# ir-tara-h.net
KiCad netlist of a schematic drawn in Altium Designer
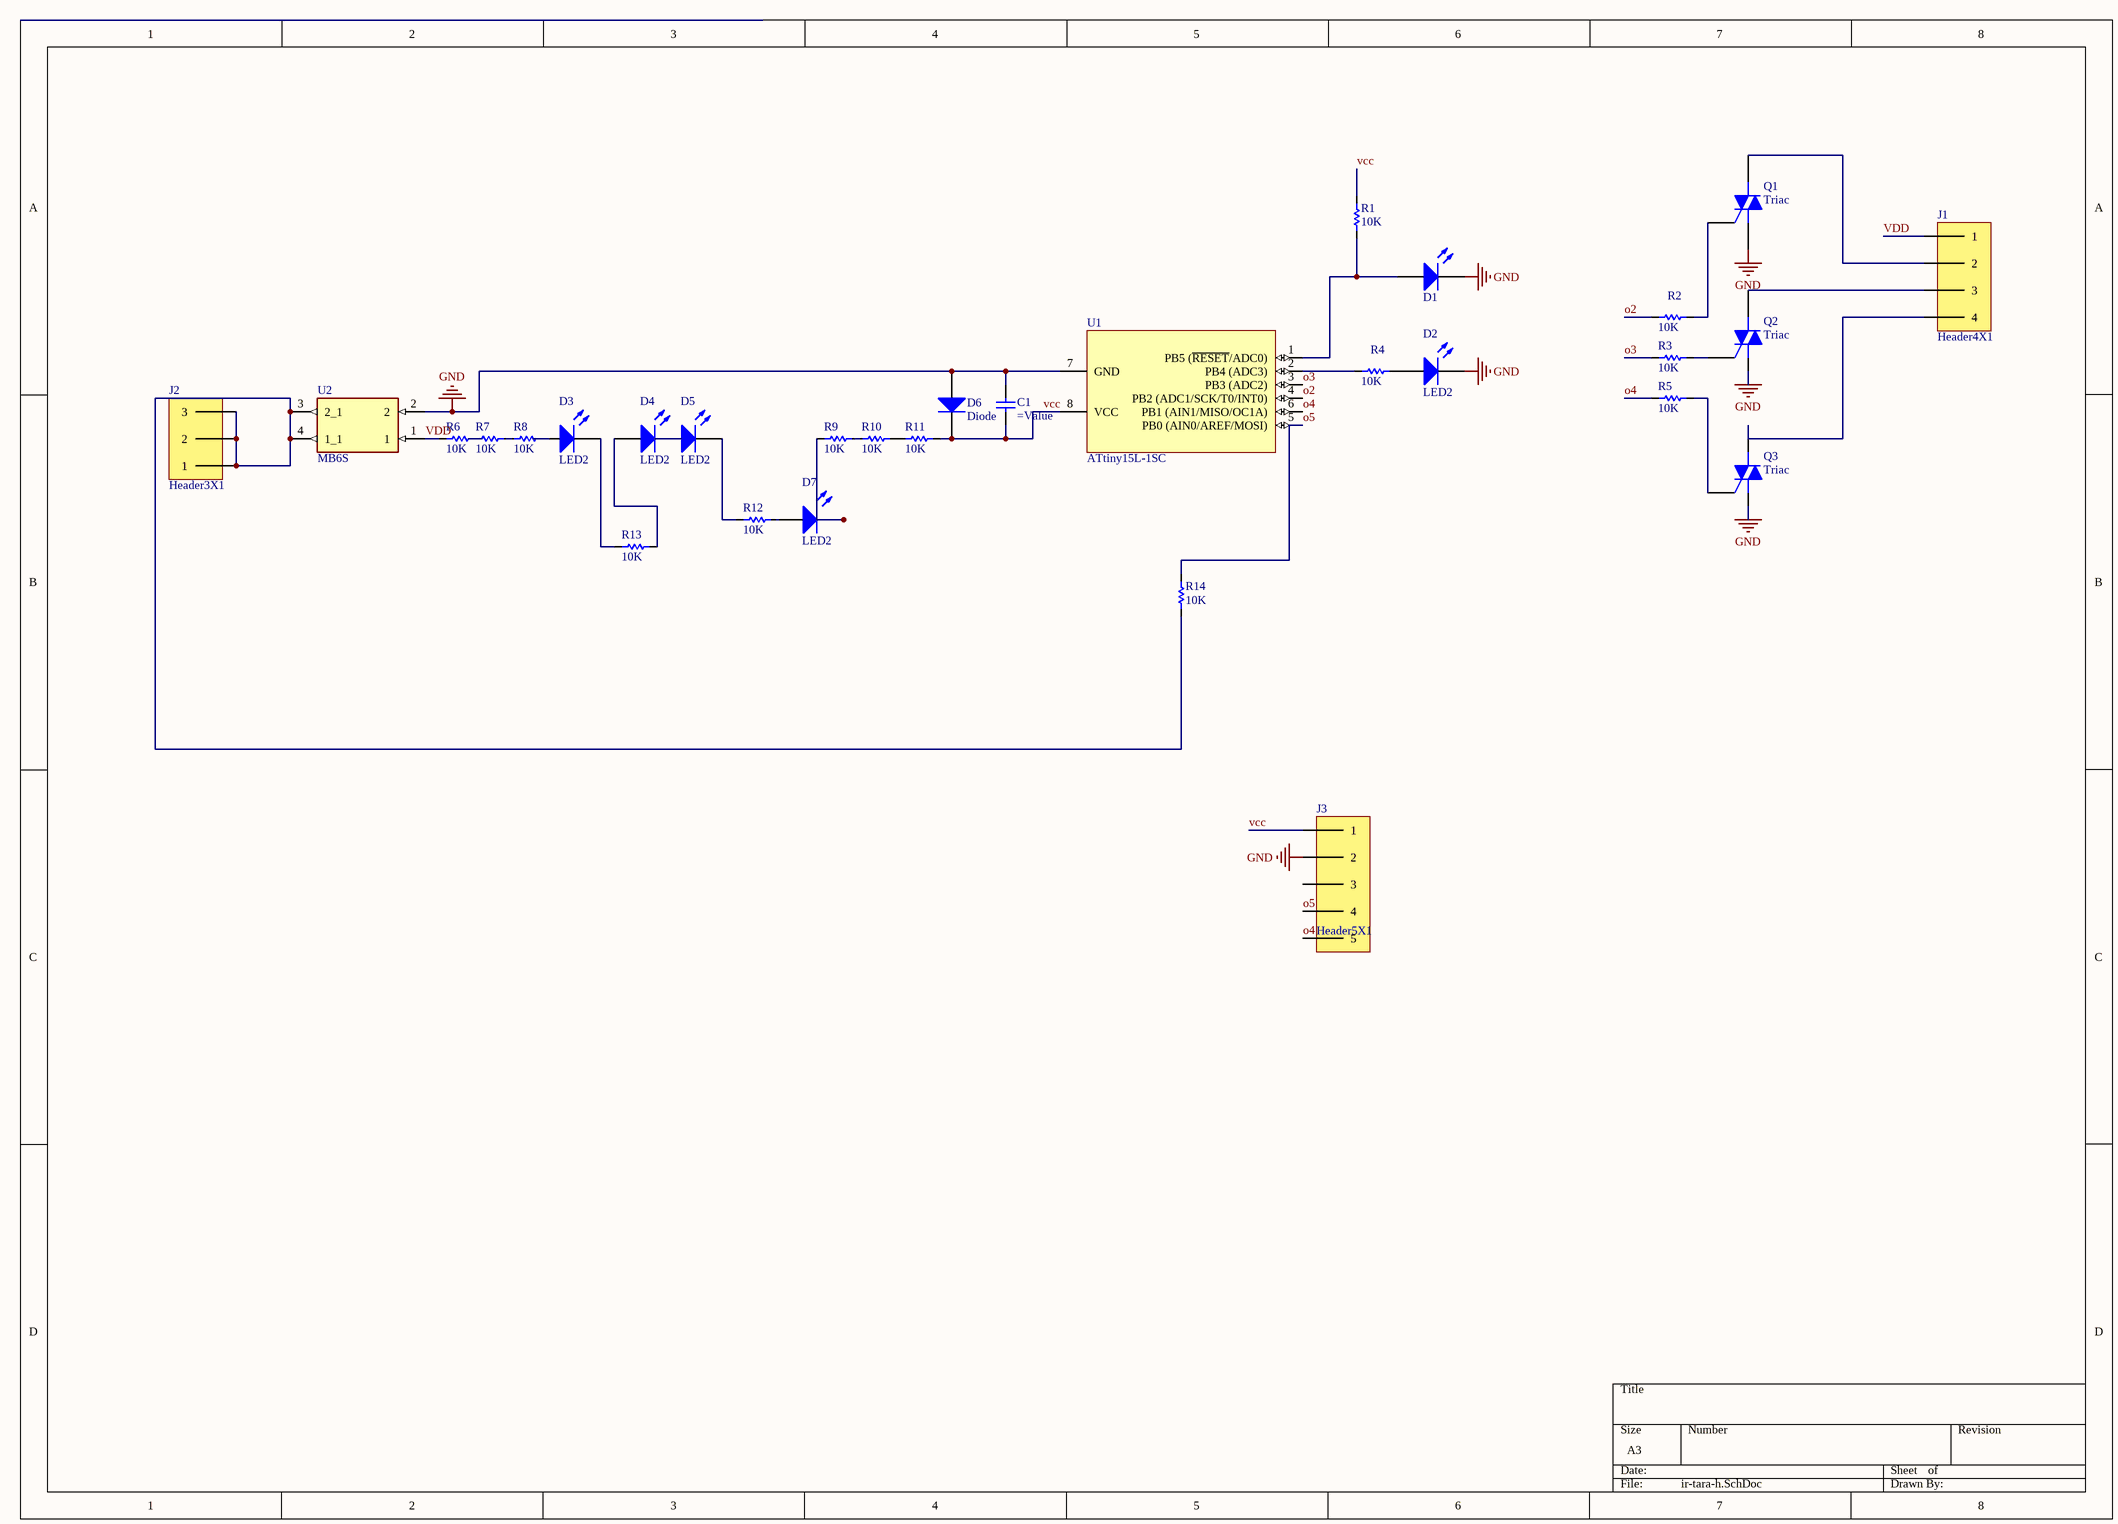
[diagram p0: ir-tara-h.SchDoc]

(export (version "E")
  (design (tool "Eeschema 10.0.6"))
  (components
    (comp (ref "C1")
      (value "~")
      (footprint "CAP 1206")
      (description "Capacitor")
      (libsource (lib "AltiumLib1") (part "Capacitor"))
    )
    (comp (ref "D1")
      (value "LED 3mm")
      (footprint "LED-3mm")
      (description "Typical LED")
      (fields (field (name "DESIGNER") "Seyed Mohsen Ghasemian") (field (name "PUBLISHER") "www.picpars.com"))
      (libsource (lib "PicPars.com_usefully_Library") (part "LED 3mm"))
    )
    (comp (ref "D2")
      (value "LED2")
      (footprint "3.2X1.6X1.1")
      (description "Typical RED, GREEN, YELLOW, AMBER GaAs LED")
      (fields (field (name "PUBLISHER") "Altium Limited"))
      (libsource (lib "Miscellaneous Devices") (part "LED2"))
    )
    (comp (ref "D3")
      (value "LED2")
      (footprint "3.2X1.6X1.1")
      (description "Typical RED, GREEN, YELLOW, AMBER GaAs LED")
      (fields (field (name "PUBLISHER") "Altium Limited"))
      (libsource (lib "Miscellaneous Devices") (part "LED2"))
    )
    (comp (ref "D4")
      (value "LED2")
      (footprint "3.2X1.6X1.1")
      (description "Typical RED, GREEN, YELLOW, AMBER GaAs LED")
      (fields (field (name "PUBLISHER") "Altium Limited"))
      (libsource (lib "Miscellaneous Devices") (part "LED2"))
    )
    (comp (ref "D5")
      (value "LED2")
      (footprint "3.2X1.6X1.1")
      (description "Typical RED, GREEN, YELLOW, AMBER GaAs LED")
      (fields (field (name "PUBLISHER") "Altium Limited"))
      (libsource (lib "Miscellaneous Devices") (part "LED2"))
    )
    (comp (ref "D6")
      (value "Diode")
      (footprint "C1206")
      (description "Default Diode")
      (fields (field (name "PUBLISHER") "Altium Limited"))
      (libsource (lib "Miscellaneous Devices") (part "Diode"))
    )
    (comp (ref "D7")
      (value "LED2")
      (footprint "3.2X1.6X1.1")
      (description "Typical RED, GREEN, YELLOW, AMBER GaAs LED")
      (fields (field (name "PUBLISHER") "Altium Limited"))
      (libsource (lib "Miscellaneous Devices") (part "LED2"))
    )
    (comp (ref "J1")
      (value "Header4X1")
      (footprint "HEADER 4X1")
      (libsource (lib "AltiumLib1") (part "Header4X1"))
    )
    (comp (ref "J2")
      (value "Header3X1")
      (footprint "HEADER 3X1")
      (libsource (lib "AltiumLib1") (part "Header3X1"))
    )
    (comp (ref "J3")
      (value "Header5X1")
      (footprint "HEADER 5X1")
      (libsource (lib "AltiumLib1") (part "Header5X1"))
    )
    (comp (ref "Q1")
      (value "Triac")
      (footprint "SOT89N")
      (description "Silicon Bidirectional Triode Thyristor")
      (fields (field (name "PUBLISHER") "Altium Limited"))
      (libsource (lib "Miscellaneous Devices") (part "Triac"))
    )
    (comp (ref "Q2")
      (value "Triac")
      (footprint "SOT89N")
      (description "Silicon Bidirectional Triode Thyristor")
      (fields (field (name "PUBLISHER") "Altium Limited"))
      (libsource (lib "Miscellaneous Devices") (part "Triac"))
    )
    (comp (ref "Q3")
      (value "Triac")
      (footprint "SOT89N")
      (description "Silicon Bidirectional Triode Thyristor")
      (fields (field (name "PUBLISHER") "Altium Limited"))
      (libsource (lib "Miscellaneous Devices") (part "Triac"))
    )
    (comp (ref "R1")
      (value "10K")
      (footprint "RES 1206 (3216X08L)")
      (description "Resistor")
      (fields (field (name "TOLERANCE") "5%") (field (name "POWER") "1/4 W"))
      (libsource (lib "AltiumLib1") (part "Resistor"))
    )
    (comp (ref "R2")
      (value "10K")
      (footprint "RES 1206 (3216X08L)")
      (description "Resistor")
      (fields (field (name "TOLERANCE") "5%") (field (name "POWER") "1/4 W"))
      (libsource (lib "AltiumLib1") (part "Resistor"))
    )
    (comp (ref "R3")
      (value "10K")
      (footprint "RES 1206 (3216X08L)")
      (description "Resistor")
      (fields (field (name "TOLERANCE") "5%") (field (name "POWER") "1/4 W"))
      (libsource (lib "AltiumLib1") (part "Resistor"))
    )
    (comp (ref "R4")
      (value "10K")
      (footprint "RES 1206 (3216X08L)")
      (description "Resistor")
      (fields (field (name "TOLERANCE") "5%") (field (name "POWER") "1/4 W"))
      (libsource (lib "AltiumLib1") (part "Resistor"))
    )
    (comp (ref "R5")
      (value "10K")
      (footprint "RES 1206 (3216X08L)")
      (description "Resistor")
      (fields (field (name "TOLERANCE") "5%") (field (name "POWER") "1/4 W"))
      (libsource (lib "AltiumLib1") (part "Resistor"))
    )
    (comp (ref "R6")
      (value "10K")
      (footprint "RES 2010 (5026X08L)")
      (description "Resistor")
      (fields (field (name "TOLERANCE") "5%") (field (name "POWER") "1/4 W"))
      (libsource (lib "AltiumLib1") (part "Resistor"))
    )
    (comp (ref "R7")
      (value "10K")
      (footprint "RES 2010 (5026X08L)")
      (description "Resistor")
      (fields (field (name "TOLERANCE") "5%") (field (name "POWER") "1/4 W"))
      (libsource (lib "AltiumLib1") (part "Resistor"))
    )
    (comp (ref "R8")
      (value "10K")
      (footprint "RES 2010 (5026X08L)")
      (description "Resistor")
      (fields (field (name "TOLERANCE") "5%") (field (name "POWER") "1/4 W"))
      (libsource (lib "AltiumLib1") (part "Resistor"))
    )
    (comp (ref "R9")
      (value "10K")
      (footprint "RES 2010 (5026X08L)")
      (description "Resistor")
      (fields (field (name "TOLERANCE") "5%") (field (name "POWER") "1/4 W"))
      (libsource (lib "AltiumLib1") (part "Resistor"))
    )
    (comp (ref "R10")
      (value "10K")
      (footprint "RES 2010 (5026X08L)")
      (description "Resistor")
      (fields (field (name "TOLERANCE") "5%") (field (name "POWER") "1/4 W"))
      (libsource (lib "AltiumLib1") (part "Resistor"))
    )
    (comp (ref "R11")
      (value "10K")
      (footprint "RES 2010 (5026X08L)")
      (description "Resistor")
      (fields (field (name "TOLERANCE") "5%") (field (name "POWER") "1/4 W"))
      (libsource (lib "AltiumLib1") (part "Resistor"))
    )
    (comp (ref "R12")
      (value "10K")
      (footprint "RES 2010 (5026X08L)")
      (description "Resistor")
      (fields (field (name "TOLERANCE") "5%") (field (name "POWER") "1/4 W"))
      (libsource (lib "AltiumLib1") (part "Resistor"))
    )
    (comp (ref "R13")
      (value "10K")
      (footprint "RES 2010 (5026X08L)")
      (description "Resistor")
      (fields (field (name "TOLERANCE") "5%") (field (name "POWER") "1/4 W"))
      (libsource (lib "AltiumLib1") (part "Resistor"))
    )
    (comp (ref "R14")
      (value "10K")
      (footprint "RES 1206 (3216X08L)")
      (description "Resistor")
      (fields (field (name "TOLERANCE") "5%") (field (name "POWER") "1/4 W"))
      (libsource (lib "AltiumLib1") (part "Resistor"))
    )
    (comp (ref "U1")
      (value "ATtiny15L-1SC")
      (footprint "8S2_N")
      (description "8-Bit AVR Microcontroller with 1K Byte of Flash Memory")
      (fields (field (name "PUBLISHER") "Altium Limited"))
      (libsource (lib "Atmel Microcontroller 8-Bit AVR") (part "ATtiny15L-1SC"))
    )
    (comp (ref "U2")
      (value "MB6S")
      (footprint "SOIC245P670X270-4N")
      (description "Bridge Rectifier Single Phase Standard 600V Surface Mount 4-SOIC")
      (fields (field (name "MF") "ON Semiconductor") (field (name "DIGI-KEY_PART_NUMBER") "MB6SCT-ND"))
      (libsource (lib "MB6S") (part "MB6S"))
    )
  )
  (nets
    (net (code "1") (name "/VDD") (class "Default")
      (node (ref "J1") (pin "1") (pinfunction "1_1") (pintype "passive"))
      (node (ref "R6") (pin "1") (pinfunction "1_1") (pintype "passive"))
      (node (ref "U2") (pin "1") (pinfunction "1_1") (pintype "input"))
    )
    (net (code "2") (name "/o2") (class "Default")
      (node (ref "R2") (pin "1") (pinfunction "1_1") (pintype "passive"))
      (node (ref "U1") (pin "4") (pinfunction "PB2_(ADC1/SCK/T0/INT0)_4") (pintype "bidirectional"))
    )
    (net (code "3") (name "/o3") (class "Default")
      (node (ref "R3") (pin "1") (pinfunction "1_1") (pintype "passive"))
      (node (ref "U1") (pin "3") (pinfunction "PB3_(ADC2)_3") (pintype "bidirectional"))
    )
    (net (code "4") (name "/o4") (class "Default")
      (node (ref "J3") (pin "5") (pinfunction "5_5") (pintype "passive"))
      (node (ref "R5") (pin "1") (pinfunction "1_1") (pintype "passive"))
      (node (ref "U1") (pin "6") (pinfunction "PB1_(AIN1/MISO/OC1A)_6") (pintype "bidirectional"))
    )
    (net (code "5") (name "/o5") (class "Default")
      (node (ref "J3") (pin "4") (pinfunction "4_4") (pintype "passive"))
      (node (ref "R14") (pin "2") (pinfunction "2_2") (pintype "passive"))
      (node (ref "U1") (pin "5") (pinfunction "PB0_(AIN0/AREF/MOSI)_5") (pintype "bidirectional"))
    )
    (net (code "6") (name "/vcc") (class "Default")
      (node (ref "C1") (pin "1") (pinfunction "+_1") (pintype "passive"))
      (node (ref "D6") (pin "2") (pinfunction "K_2") (pintype "passive"))
      (node (ref "J3") (pin "1") (pinfunction "1_1") (pintype "passive"))
      (node (ref "R1") (pin "2") (pinfunction "2_2") (pintype "passive"))
      (node (ref "R11") (pin "2") (pinfunction "2_2") (pintype "passive"))
      (node (ref "U1") (pin "8") (pinfunction "VCC_8") (pintype "power_in"))
    )
    (net (code "7") (name "GND") (class "Default")
      (node (ref "C1") (pin "2") (pinfunction "-_2") (pintype "passive"))
      (node (ref "D1") (pin "2") (pinfunction "K_2") (pintype "passive"))
      (node (ref "D2") (pin "2") (pinfunction "K_2") (pintype "passive"))
      (node (ref "D6") (pin "1") (pinfunction "A_1") (pintype "passive"))
      (node (ref "J3") (pin "2") (pinfunction "2_2") (pintype "passive"))
      (node (ref "Q1") (pin "1") (pinfunction "M1_1") (pintype "passive"))
      (node (ref "Q2") (pin "1") (pinfunction "M1_1") (pintype "passive"))
      (node (ref "Q3") (pin "1") (pinfunction "M1_1") (pintype "passive"))
      (node (ref "U1") (pin "7") (pinfunction "GND_7") (pintype "power_in"))
      (node (ref "U2") (pin "2") (pinfunction "2_2") (pintype "input"))
    )
    (net (code "8") (name "Net-(D1-A)") (class "Default")
      (node (ref "D1") (pin "1") (pinfunction "A_1") (pintype "passive"))
      (node (ref "R1") (pin "1") (pinfunction "1_1") (pintype "passive"))
      (node (ref "U1") (pin "1") (pinfunction "PB5_(~{RESET}/ADC0)_1") (pintype "bidirectional"))
    )
    (net (code "9") (name "Net-(D2-A)") (class "Default")
      (node (ref "D2") (pin "1") (pinfunction "A_1") (pintype "passive"))
      (node (ref "R4") (pin "2") (pinfunction "2_2") (pintype "passive"))
    )
    (net (code "10") (name "Net-(D3-A)") (class "Default")
      (node (ref "D3") (pin "1") (pinfunction "A_1") (pintype "passive"))
      (node (ref "R8") (pin "2") (pinfunction "2_2") (pintype "passive"))
    )
    (net (code "11") (name "Net-(D3-K)") (class "Default")
      (node (ref "D3") (pin "2") (pinfunction "K_2") (pintype "passive"))
      (node (ref "R13") (pin "1") (pinfunction "1_1") (pintype "passive"))
    )
    (net (code "12") (name "Net-(D4-A)") (class "Default")
      (node (ref "D4") (pin "1") (pinfunction "A_1") (pintype "passive"))
      (node (ref "R13") (pin "2") (pinfunction "2_2") (pintype "passive"))
    )
    (net (code "13") (name "Net-(D4-K)") (class "Default")
      (node (ref "D4") (pin "2") (pinfunction "K_2") (pintype "passive"))
      (node (ref "D5") (pin "1") (pinfunction "A_1") (pintype "passive"))
    )
    (net (code "14") (name "Net-(D5-K)") (class "Default")
      (node (ref "D5") (pin "2") (pinfunction "K_2") (pintype "passive"))
      (node (ref "R12") (pin "1") (pinfunction "1_1") (pintype "passive"))
    )
    (net (code "15") (name "Net-(D7-A)") (class "Default")
      (node (ref "D7") (pin "1") (pinfunction "A_1") (pintype "passive"))
      (node (ref "R12") (pin "2") (pinfunction "2_2") (pintype "passive"))
    )
    (net (code "16") (name "Net-(D7-K)") (class "Default")
      (node (ref "D7") (pin "2") (pinfunction "K_2") (pintype "passive"))
      (node (ref "R9") (pin "1") (pinfunction "1_1") (pintype "passive"))
    )
    (net (code "17") (name "Net-(Q1-G)") (class "Default")
      (node (ref "Q1") (pin "3") (pinfunction "G_3") (pintype "passive"))
      (node (ref "R2") (pin "2") (pinfunction "2_2") (pintype "passive"))
    )
    (net (code "18") (name "Net-(Q1-M2)") (class "Default")
      (node (ref "J1") (pin "2") (pinfunction "2_2") (pintype "passive"))
      (node (ref "Q1") (pin "2") (pinfunction "M2_2") (pintype "passive"))
    )
    (net (code "19") (name "Net-(Q2-G)") (class "Default")
      (node (ref "Q2") (pin "3") (pinfunction "G_3") (pintype "passive"))
      (node (ref "R3") (pin "2") (pinfunction "2_2") (pintype "passive"))
    )
    (net (code "20") (name "Net-(Q2-M2)") (class "Default")
      (node (ref "J1") (pin "3") (pinfunction "3_3") (pintype "passive"))
      (node (ref "Q2") (pin "2") (pinfunction "M2_2") (pintype "passive"))
    )
    (net (code "21") (name "Net-(Q3-G)") (class "Default")
      (node (ref "Q3") (pin "3") (pinfunction "G_3") (pintype "passive"))
      (node (ref "R5") (pin "2") (pinfunction "2_2") (pintype "passive"))
    )
    (net (code "22") (name "Net-(Q3-M2)") (class "Default")
      (node (ref "J1") (pin "4") (pinfunction "4_4") (pintype "passive"))
      (node (ref "Q3") (pin "2") (pinfunction "M2_2") (pintype "passive"))
    )
    (net (code "23") (name "Net-(R6-Pad2)") (class "Default")
      (node (ref "R6") (pin "2") (pinfunction "2_2") (pintype "passive"))
      (node (ref "R7") (pin "1") (pinfunction "1_1") (pintype "passive"))
    )
    (net (code "24") (name "Net-(R7-Pad2)") (class "Default")
      (node (ref "R7") (pin "2") (pinfunction "2_2") (pintype "passive"))
      (node (ref "R8") (pin "1") (pinfunction "1_1") (pintype "passive"))
    )
    (net (code "25") (name "Net-(R10-Pad1)") (class "Default")
      (node (ref "R10") (pin "1") (pinfunction "1_1") (pintype "passive"))
      (node (ref "R9") (pin "2") (pinfunction "2_2") (pintype "passive"))
    )
    (net (code "26") (name "Net-(R10-Pad2)") (class "Default")
      (node (ref "R10") (pin "2") (pinfunction "2_2") (pintype "passive"))
      (node (ref "R11") (pin "1") (pinfunction "1_1") (pintype "passive"))
    )
    (net (code "27") (name "Net-(U1-PB4_(ADC3))") (class "Default")
      (node (ref "R4") (pin "1") (pinfunction "1_1") (pintype "passive"))
      (node (ref "U1") (pin "2") (pinfunction "PB4_(ADC3)_2") (pintype "bidirectional"))
    )
    (net (code "28") (name "Net-(U2-1_1)") (class "Default")
      (node (ref "J2") (pin "1") (pinfunction "1_1") (pintype "passive"))
      (node (ref "J2") (pin "2") (pinfunction "2_2") (pintype "passive"))
      (node (ref "J2") (pin "3") (pinfunction "3_3") (pintype "passive"))
      (node (ref "R14") (pin "1") (pinfunction "1_1") (pintype "passive"))
      (node (ref "U2") (pin "3") (pinfunction "2_1_3") (pintype "output"))
      (node (ref "U2") (pin "4") (pinfunction "1_1_4") (pintype "output"))
    )
    (net (code "29") (name "unconnected-(J3-Pad3)") (class "Default")
      (node (ref "J3") (pin "3") (pinfunction "3_3") (pintype "passive"))
    )
  )
)
